# GL852-2.net
KiCad netlist of a schematic drawn in Altium Designer
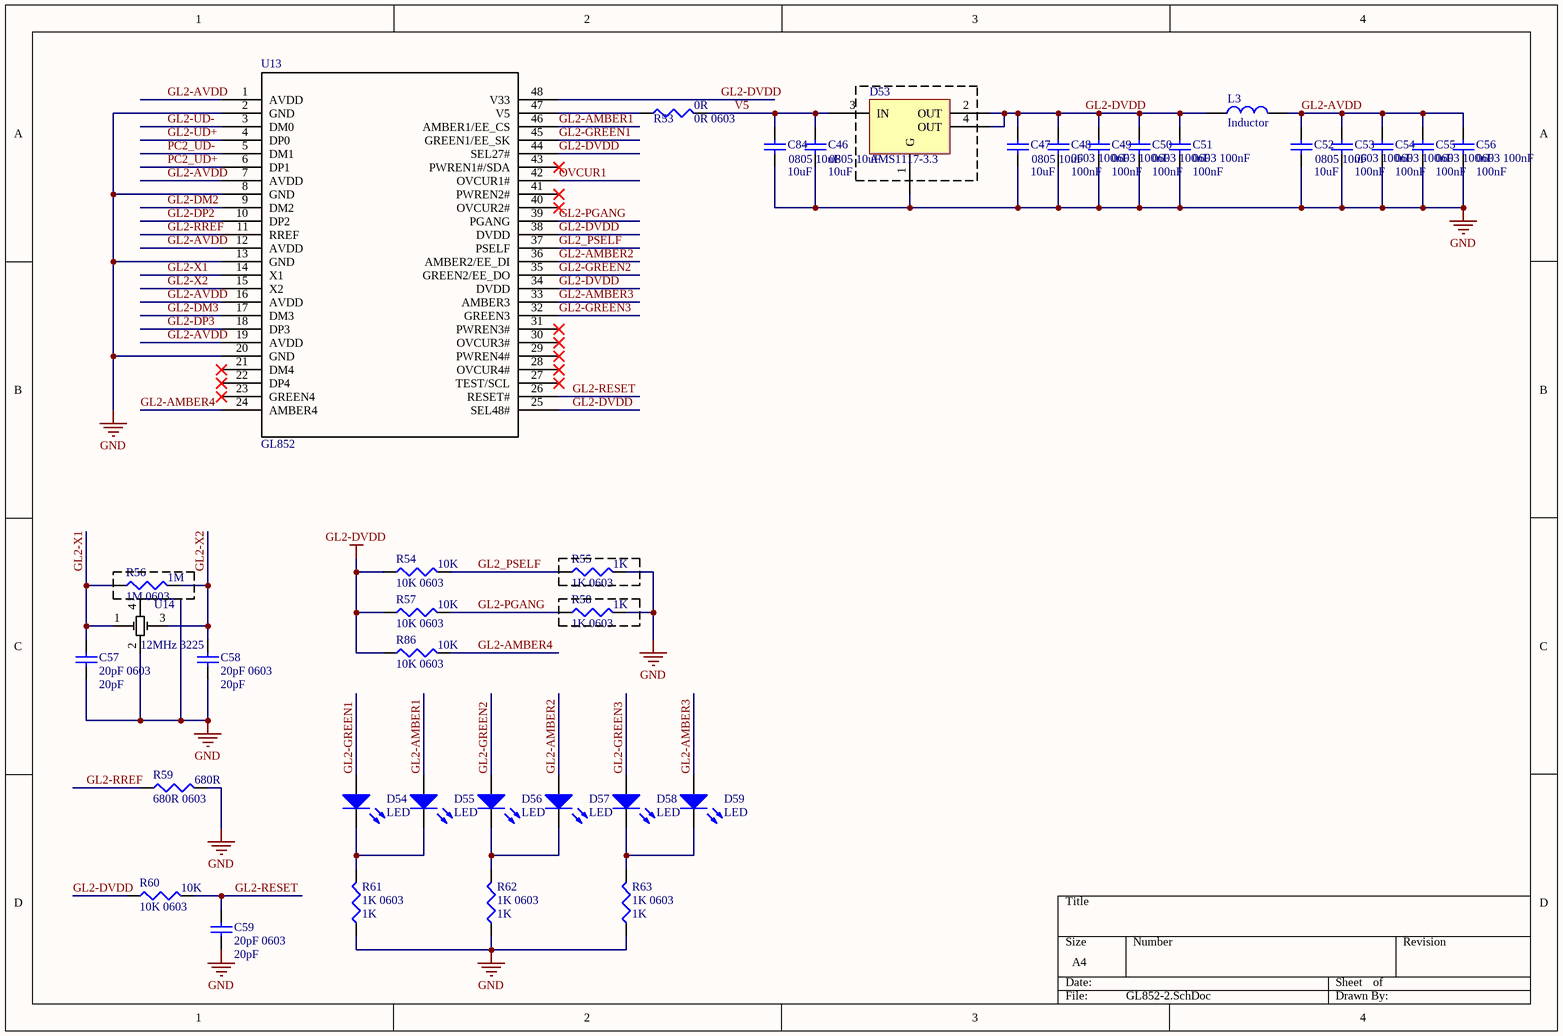
[diagram p0: GL852-2.SchDoc]

(export (version "E")
  (design (tool "Eeschema 10.0.6"))
  (components
    (comp (ref "C46")
      (value "0805 10uF")
      (footprint "C0805")
      (description "Capacitor (Semiconductor SIM Model)")
      (fields (field (name "ALTIUM_VALUE") "10uF") (field (name "PUBLISHER") "Altium Limited"))
      (libsource (lib "Miscellaneous Devices") (part "Cap Semi"))
    )
    (comp (ref "C47")
      (value "0805 10uF")
      (footprint "C0805")
      (description "Capacitor (Semiconductor SIM Model)")
      (fields (field (name "ALTIUM_VALUE") "10uF") (field (name "PUBLISHER") "Altium Limited"))
      (libsource (lib "Miscellaneous Devices") (part "Cap Semi"))
    )
    (comp (ref "C48")
      (value "0603 100nF")
      (footprint "C0603")
      (description "Capacitor (Semiconductor SIM Model)")
      (fields (field (name "ALTIUM_VALUE") "100nF") (field (name "PUBLISHER") "Altium Limited"))
      (libsource (lib "Miscellaneous Devices") (part "Cap Semi"))
    )
    (comp (ref "C49")
      (value "0603 100nF")
      (footprint "C0603")
      (description "Capacitor (Semiconductor SIM Model)")
      (fields (field (name "ALTIUM_VALUE") "100nF") (field (name "PUBLISHER") "Altium Limited"))
      (libsource (lib "Miscellaneous Devices") (part "Cap Semi"))
    )
    (comp (ref "C50")
      (value "0603 100nF")
      (footprint "C0603")
      (description "Capacitor (Semiconductor SIM Model)")
      (fields (field (name "ALTIUM_VALUE") "100nF") (field (name "PUBLISHER") "Altium Limited"))
      (libsource (lib "Miscellaneous Devices") (part "Cap Semi"))
    )
    (comp (ref "C51")
      (value "0603 100nF")
      (footprint "C0603")
      (description "Capacitor (Semiconductor SIM Model)")
      (fields (field (name "ALTIUM_VALUE") "100nF") (field (name "PUBLISHER") "Altium Limited"))
      (libsource (lib "Miscellaneous Devices") (part "Cap Semi"))
    )
    (comp (ref "C52")
      (value "0805 10uF")
      (footprint "C0805")
      (description "Capacitor (Semiconductor SIM Model)")
      (fields (field (name "ALTIUM_VALUE") "10uF") (field (name "PUBLISHER") "Altium Limited"))
      (libsource (lib "Miscellaneous Devices") (part "Cap Semi"))
    )
    (comp (ref "C53")
      (value "0603 100nF")
      (footprint "C0603")
      (description "Capacitor (Semiconductor SIM Model)")
      (fields (field (name "ALTIUM_VALUE") "100nF") (field (name "PUBLISHER") "Altium Limited"))
      (libsource (lib "Miscellaneous Devices") (part "Cap Semi"))
    )
    (comp (ref "C54")
      (value "0603 100nF")
      (footprint "C0603")
      (description "Capacitor (Semiconductor SIM Model)")
      (fields (field (name "ALTIUM_VALUE") "100nF") (field (name "PUBLISHER") "Altium Limited"))
      (libsource (lib "Miscellaneous Devices") (part "Cap Semi"))
    )
    (comp (ref "C55")
      (value "0603 100nF")
      (footprint "C0603")
      (description "Capacitor (Semiconductor SIM Model)")
      (fields (field (name "ALTIUM_VALUE") "100nF") (field (name "PUBLISHER") "Altium Limited"))
      (libsource (lib "Miscellaneous Devices") (part "Cap Semi"))
    )
    (comp (ref "C56")
      (value "0603 100nF")
      (footprint "C0603")
      (description "Capacitor (Semiconductor SIM Model)")
      (fields (field (name "ALTIUM_VALUE") "100nF") (field (name "PUBLISHER") "Altium Limited"))
      (libsource (lib "Miscellaneous Devices") (part "Cap Semi"))
    )
    (comp (ref "C57")
      (value "20pF 0603")
      (footprint "C0603")
      (description "Capacitor (Semiconductor SIM Model)")
      (fields (field (name "ALTIUM_VALUE") "20pF") (field (name "PUBLISHER") "Altium Limited"))
      (libsource (lib "Miscellaneous Devices") (part "Cap Semi"))
    )
    (comp (ref "C58")
      (value "20pF 0603")
      (footprint "C0603")
      (description "Capacitor (Semiconductor SIM Model)")
      (fields (field (name "ALTIUM_VALUE") "20pF") (field (name "PUBLISHER") "Altium Limited"))
      (libsource (lib "Miscellaneous Devices") (part "Cap Semi"))
    )
    (comp (ref "C59")
      (value "20pF 0603")
      (footprint "C0603")
      (description "Capacitor (Semiconductor SIM Model)")
      (fields (field (name "ALTIUM_VALUE") "20pF") (field (name "PUBLISHER") "Altium Limited"))
      (libsource (lib "Miscellaneous Devices") (part "Cap Semi"))
    )
    (comp (ref "C84")
      (value "0805 10uF")
      (footprint "C0805")
      (description "Capacitor (Semiconductor SIM Model)")
      (fields (field (name "ALTIUM_VALUE") "10uF") (field (name "PUBLISHER") "Altium Limited"))
      (libsource (lib "Miscellaneous Devices") (part "Cap Semi"))
    )
    (comp (ref "D53")
      (value "AMS1117-3.3")
      (footprint "SOT-223")
      (libsource (lib "MyLib") (part "AMS1117-3.3"))
    )
    (comp (ref "D54") (value "LED") (footprint "LED0603") (libsource (lib "Common Device") (part "LED")))
    (comp (ref "D55") (value "LED") (footprint "LED0603") (libsource (lib "Common Device") (part "LED")))
    (comp (ref "D56") (value "LED") (footprint "LED0603") (libsource (lib "Common Device") (part "LED")))
    (comp (ref "D57") (value "LED") (footprint "LED0603") (libsource (lib "Common Device") (part "LED")))
    (comp (ref "D58") (value "LED") (footprint "LED0603") (libsource (lib "Common Device") (part "LED")))
    (comp (ref "D59") (value "LED") (footprint "LED0603") (libsource (lib "Common Device") (part "LED")))
    (comp (ref "L3")
      (value "Inductor")
      (footprint "L0603")
      (libsource (lib "Common Device") (part "Inductor"))
    )
    (comp (ref "R53")
      (value "0R 0603")
      (footprint "R0603")
      (description "Resistor")
      (fields (field (name "ALTIUM_VALUE") "0R") (field (name "PUBLISHER") "Altium Limited"))
      (libsource (lib "Miscellaneous Devices") (part "Res3"))
    )
    (comp (ref "R54")
      (value "10K 0603")
      (footprint "R0603")
      (description "Resistor")
      (fields (field (name "ALTIUM_VALUE") "10K") (field (name "PUBLISHER") "Altium Limited"))
      (libsource (lib "Miscellaneous Devices") (part "Res3"))
    )
    (comp (ref "R55")
      (value "1K 0603")
      (footprint "R0603")
      (description "Resistor")
      (fields (field (name "ALTIUM_VALUE") "1K") (field (name "PUBLISHER") "Altium Limited"))
      (libsource (lib "Miscellaneous Devices") (part "Res3"))
    )
    (comp (ref "R56")
      (value "1M 0603")
      (footprint "R0603")
      (description "Resistor")
      (fields (field (name "ALTIUM_VALUE") "1M") (field (name "PUBLISHER") "Altium Limited"))
      (libsource (lib "Miscellaneous Devices") (part "Res3"))
    )
    (comp (ref "R57")
      (value "10K 0603")
      (footprint "R0603")
      (description "Resistor")
      (fields (field (name "ALTIUM_VALUE") "10K") (field (name "PUBLISHER") "Altium Limited"))
      (libsource (lib "Miscellaneous Devices") (part "Res3"))
    )
    (comp (ref "R58")
      (value "1K 0603")
      (footprint "R0603")
      (description "Resistor")
      (fields (field (name "ALTIUM_VALUE") "1K") (field (name "PUBLISHER") "Altium Limited"))
      (libsource (lib "Miscellaneous Devices") (part "Res3"))
    )
    (comp (ref "R59")
      (value "680R 0603")
      (footprint "R0603")
      (description "Resistor")
      (fields (field (name "ALTIUM_VALUE") "680R") (field (name "PUBLISHER") "Altium Limited"))
      (libsource (lib "Miscellaneous Devices") (part "Res3"))
    )
    (comp (ref "R60")
      (value "10K 0603")
      (footprint "R0603")
      (description "Resistor")
      (fields (field (name "ALTIUM_VALUE") "10K") (field (name "PUBLISHER") "Altium Limited"))
      (libsource (lib "Miscellaneous Devices") (part "Res3"))
    )
    (comp (ref "R61")
      (value "1K 0603")
      (footprint "R0603")
      (description "Resistor")
      (fields (field (name "ALTIUM_VALUE") "1K") (field (name "PUBLISHER") "Altium Limited"))
      (libsource (lib "Miscellaneous Devices") (part "Res3"))
    )
    (comp (ref "R62")
      (value "1K 0603")
      (footprint "R0603")
      (description "Resistor")
      (fields (field (name "ALTIUM_VALUE") "1K") (field (name "PUBLISHER") "Altium Limited"))
      (libsource (lib "Miscellaneous Devices") (part "Res3"))
    )
    (comp (ref "R63")
      (value "1K 0603")
      (footprint "R0603")
      (description "Resistor")
      (fields (field (name "ALTIUM_VALUE") "1K") (field (name "PUBLISHER") "Altium Limited"))
      (libsource (lib "Miscellaneous Devices") (part "Res3"))
    )
    (comp (ref "R86")
      (value "10K 0603")
      (footprint "R0603")
      (description "Resistor")
      (fields (field (name "ALTIUM_VALUE") "10K") (field (name "PUBLISHER") "Altium Limited"))
      (libsource (lib "Miscellaneous Devices") (part "Res3"))
    )
    (comp (ref "U13")
      (value "GL852")
      (footprint "qfp48-20-0909b")
      (description "Imported")
      (libsource (lib "USB-new-component") (part "GL852"))
    )
    (comp (ref "U14")
      (value "12MHz 3225")
      (footprint "XTAL-3225")
      (libsource (lib "XTAL3225") (part "Component_1"))
    )
  )
  (nets
    (net (code "1") (name "/GL2-AMBER1") (class "Default")
      (node (ref "D55") (pin "1") (pinfunction "A_1") (pintype "passive"))
      (node (ref "U13") (pin "46") (pinfunction "AMBER1/EE_CS_46") (pintype "passive"))
    )
    (net (code "2") (name "/GL2-AMBER2") (class "Default")
      (node (ref "D57") (pin "1") (pinfunction "A_1") (pintype "passive"))
      (node (ref "U13") (pin "36") (pinfunction "AMBER2/EE_DI_36") (pintype "passive"))
    )
    (net (code "3") (name "/GL2-AMBER3") (class "Default")
      (node (ref "D59") (pin "1") (pinfunction "A_1") (pintype "passive"))
      (node (ref "U13") (pin "33") (pinfunction "AMBER3_33") (pintype "passive"))
    )
    (net (code "4") (name "/GL2-AMBER4") (class "Default")
      (node (ref "R86") (pin "2") (pinfunction "2_2") (pintype "passive"))
      (node (ref "U13") (pin "24") (pinfunction "AMBER4_24") (pintype "passive"))
    )
    (net (code "5") (name "/GL2-AVDD") (class "Default")
      (node (ref "C52") (pin "2") (pinfunction "2_2") (pintype "passive"))
      (node (ref "C53") (pin "2") (pinfunction "2_2") (pintype "passive"))
      (node (ref "C54") (pin "2") (pinfunction "2_2") (pintype "passive"))
      (node (ref "C55") (pin "2") (pinfunction "2_2") (pintype "passive"))
      (node (ref "C56") (pin "2") (pinfunction "2_2") (pintype "passive"))
      (node (ref "L3") (pin "2") (pinfunction "2_2") (pintype "passive"))
      (node (ref "U13") (pin "1") (pinfunction "AVDD_1") (pintype "passive"))
      (node (ref "U13") (pin "12") (pinfunction "AVDD_12") (pintype "passive"))
      (node (ref "U13") (pin "16") (pinfunction "AVDD_16") (pintype "passive"))
      (node (ref "U13") (pin "19") (pinfunction "AVDD_19") (pintype "passive"))
      (node (ref "U13") (pin "7") (pinfunction "AVDD_7") (pintype "passive"))
    )
    (net (code "6") (name "/GL2-DM2") (class "Default")
      (node (ref "U13") (pin "9") (pinfunction "DM2_9") (pintype "passive"))
    )
    (net (code "7") (name "/GL2-DM3") (class "Default")
      (node (ref "U13") (pin "17") (pinfunction "DM3_17") (pintype "passive"))
    )
    (net (code "8") (name "/GL2-DP2") (class "Default")
      (node (ref "U13") (pin "10") (pinfunction "DP2_10") (pintype "passive"))
    )
    (net (code "9") (name "/GL2-DP3") (class "Default")
      (node (ref "U13") (pin "18") (pinfunction "DP3_18") (pintype "passive"))
    )
    (net (code "10") (name "/GL2-GREEN1") (class "Default")
      (node (ref "D54") (pin "1") (pinfunction "A_1") (pintype "passive"))
      (node (ref "U13") (pin "45") (pinfunction "GREEN1/EE_SK_45") (pintype "passive"))
    )
    (net (code "11") (name "/GL2-GREEN2") (class "Default")
      (node (ref "D56") (pin "1") (pinfunction "A_1") (pintype "passive"))
      (node (ref "U13") (pin "35") (pinfunction "GREEN2/EE_DO_35") (pintype "passive"))
    )
    (net (code "12") (name "/GL2-GREEN3") (class "Default")
      (node (ref "D58") (pin "1") (pinfunction "A_1") (pintype "passive"))
      (node (ref "U13") (pin "32") (pinfunction "GREEN3_32") (pintype "passive"))
    )
    (net (code "13") (name "/GL2-PGANG") (class "Default")
      (node (ref "R57") (pin "2") (pinfunction "2_2") (pintype "passive"))
      (node (ref "R58") (pin "1") (pinfunction "1_1") (pintype "passive"))
      (node (ref "U13") (pin "39") (pinfunction "PGANG_39") (pintype "passive"))
    )
    (net (code "14") (name "/GL2-RESET") (class "Default")
      (node (ref "C59") (pin "2") (pinfunction "2_2") (pintype "passive"))
      (node (ref "R60") (pin "2") (pinfunction "2_2") (pintype "passive"))
      (node (ref "U13") (pin "26") (pinfunction "RESET#_26") (pintype "passive"))
    )
    (net (code "15") (name "/GL2-RREF") (class "Default")
      (node (ref "R59") (pin "1") (pinfunction "1_1") (pintype "passive"))
      (node (ref "U13") (pin "11") (pinfunction "RREF_11") (pintype "passive"))
    )
    (net (code "16") (name "/GL2-UD+") (class "Default")
      (node (ref "U13") (pin "4") (pinfunction "DP0_4") (pintype "passive"))
    )
    (net (code "17") (name "/GL2-UD-") (class "Default")
      (node (ref "U13") (pin "3") (pinfunction "DM0_3") (pintype "passive"))
    )
    (net (code "18") (name "/GL2-X1") (class "Default")
      (node (ref "C57") (pin "2") (pinfunction "2_2") (pintype "passive"))
      (node (ref "R56") (pin "1") (pinfunction "1_1") (pintype "passive"))
      (node (ref "U13") (pin "14") (pinfunction "X1_14") (pintype "passive"))
      (node (ref "U14") (pin "1") (pinfunction "1_1") (pintype "passive"))
    )
    (net (code "19") (name "/GL2-X2") (class "Default")
      (node (ref "C58") (pin "2") (pinfunction "2_2") (pintype "passive"))
      (node (ref "R56") (pin "2") (pinfunction "2_2") (pintype "passive"))
      (node (ref "U13") (pin "15") (pinfunction "X2_15") (pintype "passive"))
      (node (ref "U14") (pin "3") (pinfunction "3_3") (pintype "passive"))
    )
    (net (code "20") (name "/GL2_PSELF") (class "Default")
      (node (ref "R54") (pin "2") (pinfunction "2_2") (pintype "passive"))
      (node (ref "R55") (pin "1") (pinfunction "1_1") (pintype "passive"))
      (node (ref "U13") (pin "37") (pinfunction "PSELF_37") (pintype "passive"))
    )
    (net (code "21") (name "/OVCUR1") (class "Default")
      (node (ref "U13") (pin "42") (pinfunction "OVCUR1#_42") (pintype "passive"))
    )
    (net (code "22") (name "/PC2_UD+") (class "Default")
      (node (ref "U13") (pin "6") (pinfunction "DP1_6") (pintype "passive"))
    )
    (net (code "23") (name "/PC2_UD-") (class "Default")
      (node (ref "U13") (pin "5") (pinfunction "DM1_5") (pintype "passive"))
    )
    (net (code "24") (name "/V5") (class "Default")
      (node (ref "C46") (pin "2") (pinfunction "2_2") (pintype "passive"))
      (node (ref "C84") (pin "2") (pinfunction "2_2") (pintype "passive"))
      (node (ref "D53") (pin "3") (pinfunction "IN_3") (pintype "passive"))
      (node (ref "R53") (pin "2") (pinfunction "2_2") (pintype "passive"))
    )
    (net (code "25") (name "GL2-DVDD") (class "Default")
      (node (ref "C47") (pin "2") (pinfunction "2_2") (pintype "passive"))
      (node (ref "C48") (pin "2") (pinfunction "2_2") (pintype "passive"))
      (node (ref "C49") (pin "2") (pinfunction "2_2") (pintype "passive"))
      (node (ref "C50") (pin "2") (pinfunction "2_2") (pintype "passive"))
      (node (ref "C51") (pin "2") (pinfunction "2_2") (pintype "passive"))
      (node (ref "D53") (pin "2") (pinfunction "OUT_2") (pintype "passive"))
      (node (ref "D53") (pin "4") (pinfunction "OUT_4") (pintype "passive"))
      (node (ref "L3") (pin "1") (pinfunction "1_1") (pintype "passive"))
      (node (ref "R54") (pin "1") (pinfunction "1_1") (pintype "passive"))
      (node (ref "R57") (pin "1") (pinfunction "1_1") (pintype "passive"))
      (node (ref "R60") (pin "1") (pinfunction "1_1") (pintype "passive"))
      (node (ref "R86") (pin "1") (pinfunction "1_1") (pintype "passive"))
      (node (ref "U13") (pin "25") (pinfunction "SEL48#_25") (pintype "passive"))
      (node (ref "U13") (pin "34") (pinfunction "DVDD_34") (pintype "passive"))
      (node (ref "U13") (pin "38") (pinfunction "DVDD_38") (pintype "passive"))
      (node (ref "U13") (pin "44") (pinfunction "SEL27#_44") (pintype "passive"))
      (node (ref "U13") (pin "48") (pinfunction "V33_48") (pintype "passive"))
    )
    (net (code "26") (name "GND") (class "Default")
      (node (ref "C46") (pin "1") (pinfunction "1_1") (pintype "passive"))
      (node (ref "C47") (pin "1") (pinfunction "1_1") (pintype "passive"))
      (node (ref "C48") (pin "1") (pinfunction "1_1") (pintype "passive"))
      (node (ref "C49") (pin "1") (pinfunction "1_1") (pintype "passive"))
      (node (ref "C50") (pin "1") (pinfunction "1_1") (pintype "passive"))
      (node (ref "C51") (pin "1") (pinfunction "1_1") (pintype "passive"))
      (node (ref "C52") (pin "1") (pinfunction "1_1") (pintype "passive"))
      (node (ref "C53") (pin "1") (pinfunction "1_1") (pintype "passive"))
      (node (ref "C54") (pin "1") (pinfunction "1_1") (pintype "passive"))
      (node (ref "C55") (pin "1") (pinfunction "1_1") (pintype "passive"))
      (node (ref "C56") (pin "1") (pinfunction "1_1") (pintype "passive"))
      (node (ref "C57") (pin "1") (pinfunction "1_1") (pintype "passive"))
      (node (ref "C58") (pin "1") (pinfunction "1_1") (pintype "passive"))
      (node (ref "C59") (pin "1") (pinfunction "1_1") (pintype "passive"))
      (node (ref "C84") (pin "1") (pinfunction "1_1") (pintype "passive"))
      (node (ref "D53") (pin "1") (pinfunction "G_1") (pintype "passive"))
      (node (ref "R55") (pin "2") (pinfunction "2_2") (pintype "passive"))
      (node (ref "R58") (pin "2") (pinfunction "2_2") (pintype "passive"))
      (node (ref "R59") (pin "2") (pinfunction "2_2") (pintype "passive"))
      (node (ref "R61") (pin "1") (pinfunction "1_1") (pintype "passive"))
      (node (ref "R62") (pin "1") (pinfunction "1_1") (pintype "passive"))
      (node (ref "R63") (pin "1") (pinfunction "1_1") (pintype "passive"))
      (node (ref "U13") (pin "13") (pinfunction "GND_13") (pintype "passive"))
      (node (ref "U13") (pin "2") (pinfunction "GND_2") (pintype "passive"))
      (node (ref "U13") (pin "20") (pinfunction "GND_20") (pintype "passive"))
      (node (ref "U13") (pin "8") (pinfunction "GND_8") (pintype "passive"))
      (node (ref "U14") (pin "2") (pinfunction "2_2") (pintype "passive"))
      (node (ref "U14") (pin "4") (pinfunction "4_4") (pintype "passive"))
    )
    (net (code "27") (name "Net-(D54-K)") (class "Default")
      (node (ref "D54") (pin "2") (pinfunction "K_2") (pintype "passive"))
      (node (ref "D55") (pin "2") (pinfunction "K_2") (pintype "passive"))
      (node (ref "R61") (pin "2") (pinfunction "2_2") (pintype "passive"))
    )
    (net (code "28") (name "Net-(D56-K)") (class "Default")
      (node (ref "D56") (pin "2") (pinfunction "K_2") (pintype "passive"))
      (node (ref "D57") (pin "2") (pinfunction "K_2") (pintype "passive"))
      (node (ref "R62") (pin "2") (pinfunction "2_2") (pintype "passive"))
    )
    (net (code "29") (name "Net-(D58-K)") (class "Default")
      (node (ref "D58") (pin "2") (pinfunction "K_2") (pintype "passive"))
      (node (ref "D59") (pin "2") (pinfunction "K_2") (pintype "passive"))
      (node (ref "R63") (pin "2") (pinfunction "2_2") (pintype "passive"))
    )
    (net (code "30") (name "Net-(U13-V5)") (class "Default")
      (node (ref "R53") (pin "1") (pinfunction "1_1") (pintype "passive"))
      (node (ref "U13") (pin "47") (pinfunction "V5_47") (pintype "passive"))
    )
    (net (code "31") (name "unconnected-(U13-DM4-Pad21)") (class "Default")
      (node (ref "U13") (pin "21") (pinfunction "DM4_21") (pintype "passive+no_connect"))
    )
    (net (code "32") (name "unconnected-(U13-DP4-Pad22)") (class "Default")
      (node (ref "U13") (pin "22") (pinfunction "DP4_22") (pintype "passive+no_connect"))
    )
    (net (code "33") (name "unconnected-(U13-GREEN4-Pad23)") (class "Default")
      (node (ref "U13") (pin "23") (pinfunction "GREEN4_23") (pintype "passive+no_connect"))
    )
    (net (code "34") (name "unconnected-(U13-OVCUR2#-Pad40)") (class "Default")
      (node (ref "U13") (pin "40") (pinfunction "OVCUR2#_40") (pintype "passive+no_connect"))
    )
    (net (code "35") (name "unconnected-(U13-OVCUR3#-Pad30)") (class "Default")
      (node (ref "U13") (pin "30") (pinfunction "OVCUR3#_30") (pintype "passive+no_connect"))
    )
    (net (code "36") (name "unconnected-(U13-OVCUR4#-Pad28)") (class "Default")
      (node (ref "U13") (pin "28") (pinfunction "OVCUR4#_28") (pintype "passive+no_connect"))
    )
    (net (code "37") (name "unconnected-(U13-PWREN1#{slash}SDA-Pad43)") (class "Default")
      (node (ref "U13") (pin "43") (pinfunction "PWREN1#/SDA_43") (pintype "passive+no_connect"))
    )
    (net (code "38") (name "unconnected-(U13-PWREN2#-Pad41)") (class "Default")
      (node (ref "U13") (pin "41") (pinfunction "PWREN2#_41") (pintype "passive+no_connect"))
    )
    (net (code "39") (name "unconnected-(U13-PWREN3#-Pad31)") (class "Default")
      (node (ref "U13") (pin "31") (pinfunction "PWREN3#_31") (pintype "passive+no_connect"))
    )
    (net (code "40") (name "unconnected-(U13-PWREN4#-Pad29)") (class "Default")
      (node (ref "U13") (pin "29") (pinfunction "PWREN4#_29") (pintype "passive+no_connect"))
    )
    (net (code "41") (name "unconnected-(U13-TEST{slash}SCL-Pad27)") (class "Default")
      (node (ref "U13") (pin "27") (pinfunction "TEST/SCL_27") (pintype "passive+no_connect"))
    )
  )
)
